# HM_Nightfall-mini-2e_Encoder-PCB-R_v1.net
KiCad netlist of a schematic drawn in EAGLE
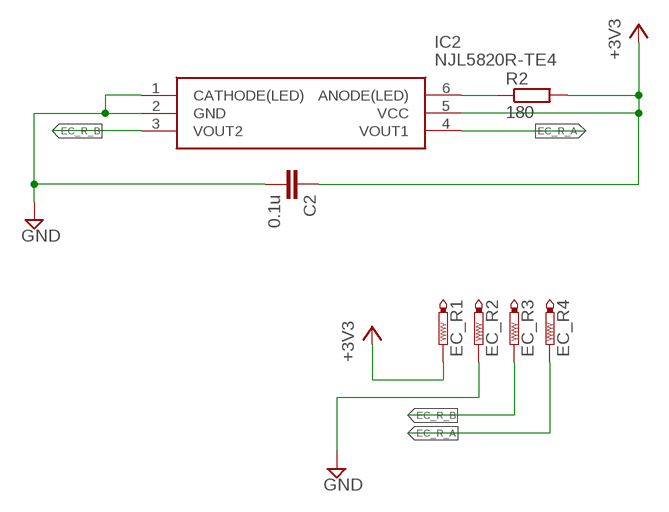
[diagram p0: schematic, sheet 1]

(export (version "E")
  (design (tool "Eeschema 10.0.6"))
  (components
    (comp (ref "C2")
      (value "0.1u")
      (footprint "eagle-import:C0402")
      (libsource (lib "eagle-import") (part "C-EUC0402"))
    )
    (comp (ref "EC_R1")
      (value "PTR1TP06SQ")
      (footprint "eagle-import:TP06SQ")
      (libsource (lib "eagle-import") (part "PTR1TP06SQ"))
    )
    (comp (ref "EC_R2")
      (value "PTR1TP06SQ")
      (footprint "eagle-import:TP06SQ")
      (libsource (lib "eagle-import") (part "PTR1TP06SQ"))
    )
    (comp (ref "EC_R3")
      (value "PTR1TP06SQ")
      (footprint "eagle-import:TP06SQ")
      (libsource (lib "eagle-import") (part "PTR1TP06SQ"))
    )
    (comp (ref "EC_R4")
      (value "PTR1TP06SQ")
      (footprint "eagle-import:TP06SQ")
      (libsource (lib "eagle-import") (part "PTR1TP06SQ"))
    )
    (comp (ref "IC2")
      (value "NJL5820R-TE4")
      (footprint "eagle-import:NJL5820RTE4")
      (fields (field (name "MOUSER_PART_NUMBER") "513-NJL5820R-TE4"))
      (libsource (lib "eagle-import") (part "NJL5820R-TE4"))
    )
    (comp (ref "R2")
      (value "180")
      (footprint "eagle-import:R0402")
      (libsource (lib "eagle-import") (part "R-EU_R0402"))
    )
  )
  (nets
    (net (code "1") (name "+3V3") (class "Default")
      (node (ref "C2") (pin "1") (pinfunction "1_1") (pintype "passive"))
      (node (ref "EC_R1") (pin "TP") (pinfunction "TP_TP") (pintype "input"))
      (node (ref "IC2") (pin "5") (pinfunction "VCC_5") (pintype "bidirectional"))
      (node (ref "R2") (pin "2") (pinfunction "2_2") (pintype "passive"))
    )
    (net (code "2") (name "EC_R_A") (class "Default")
      (node (ref "EC_R4") (pin "TP") (pinfunction "TP_TP") (pintype "input"))
      (node (ref "IC2") (pin "4") (pinfunction "VOUT1_4") (pintype "bidirectional"))
    )
    (net (code "3") (name "EC_R_B") (class "Default")
      (node (ref "EC_R3") (pin "TP") (pinfunction "TP_TP") (pintype "input"))
      (node (ref "IC2") (pin "3") (pinfunction "VOUT2_3") (pintype "bidirectional"))
    )
    (net (code "4") (name "GND") (class "Default")
      (node (ref "C2") (pin "2") (pinfunction "2_2") (pintype "passive"))
      (node (ref "EC_R2") (pin "TP") (pinfunction "TP_TP") (pintype "input"))
      (node (ref "IC2") (pin "1") (pinfunction "CATHODE(LED)_1") (pintype "bidirectional"))
      (node (ref "IC2") (pin "2") (pinfunction "GND_2") (pintype "bidirectional"))
    )
    (net (code "5") (name "Net-(IC2-ANODE(LED))") (class "Default")
      (node (ref "IC2") (pin "6") (pinfunction "ANODE(LED)_6") (pintype "bidirectional"))
      (node (ref "R2") (pin "1") (pinfunction "1_1") (pintype "passive"))
    )
  )
)
